# rapoukBoardv6.net
KiCad netlist of a schematic drawn in EasyEDA
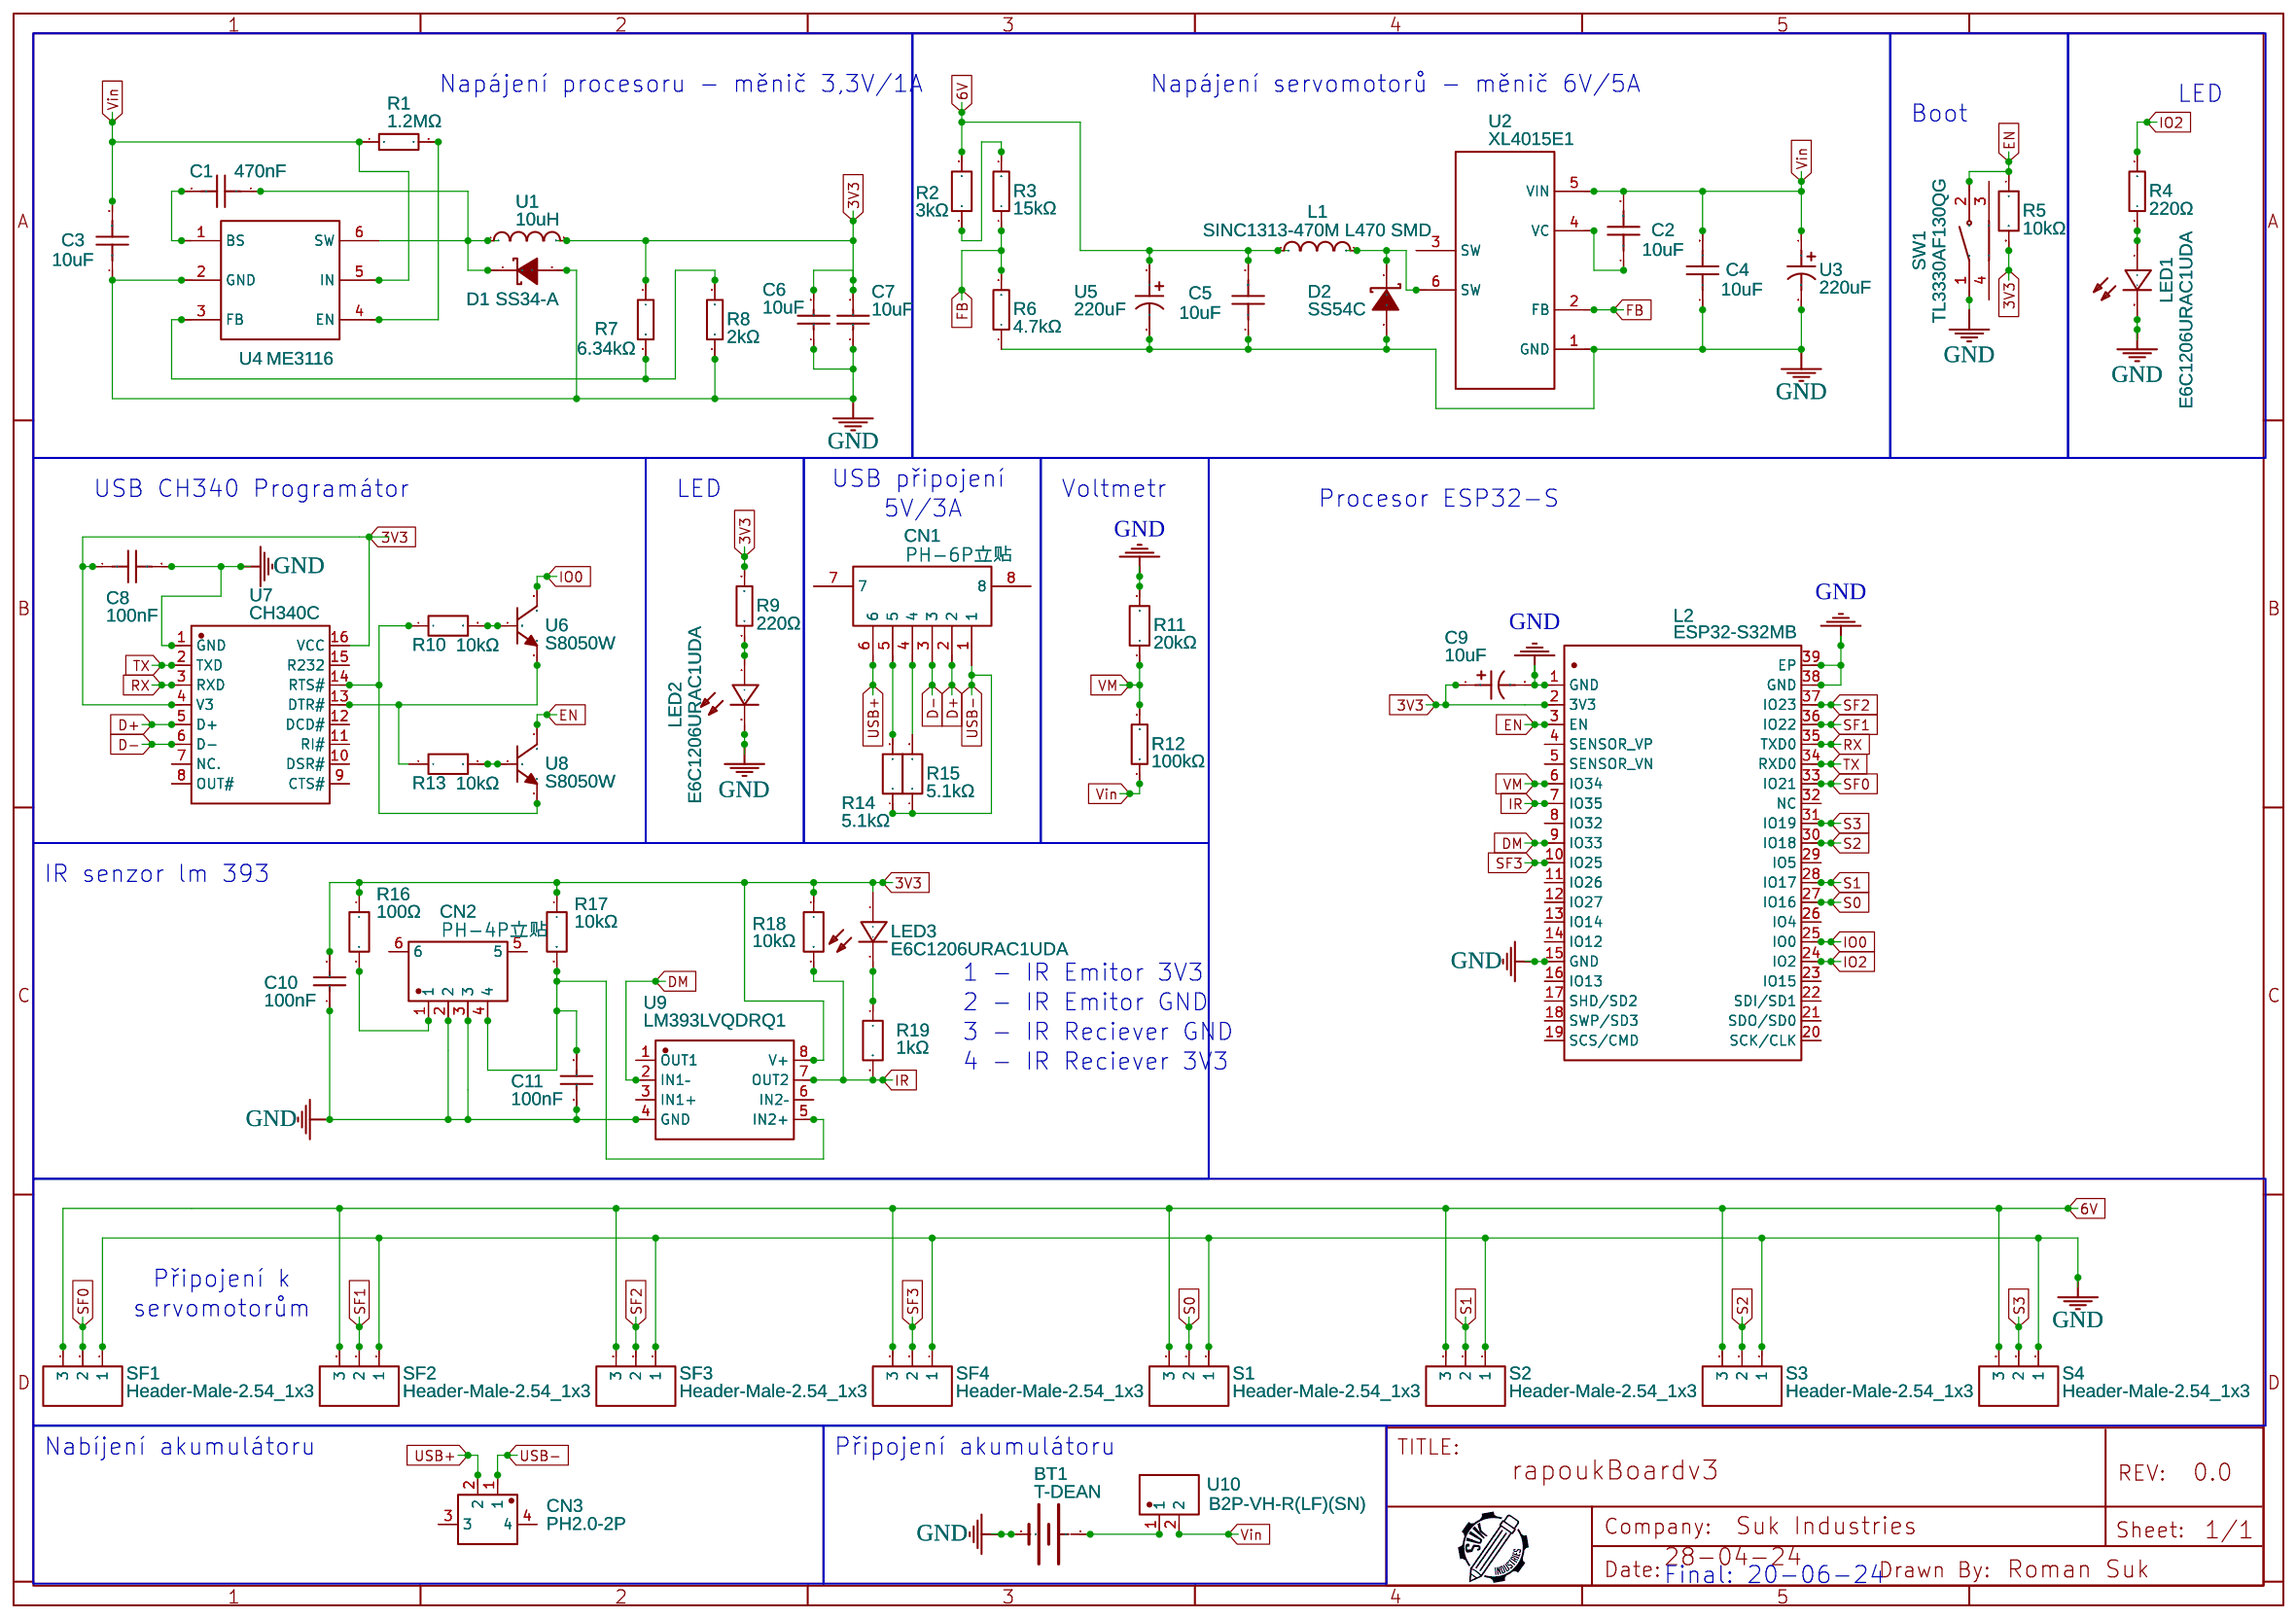
[diagram p0: schematic sheet]

(export (version "E")
  (design (tool "Eeschema 10.0.6"))
  (components
    (comp (ref "BT1") (value "T-DEAN") (libsource (lib "") (part "T-DEAN")))
    (comp (ref "C1")
      (value "470nF")
      (fields
        (field (name "Manufacturer Part") "TCC1206X7R474K500FT")
        (field (name "Manufacturer") "CCTC(三环)")
      )
      (libsource (lib "") (part "TCC1206X7R474K500FT"))
    )
    (comp (ref "C2")
      (value "10uF")
      (fields
        (field (name "Manufacturer Part") "TCC1206X7R106K250HT")
        (field (name "Manufacturer") "CCTC(三环)")
      )
      (libsource (lib "") (part "TCC1206X7R106K250HT"))
    )
    (comp (ref "C3")
      (value "10uF")
      (fields
        (field (name "Manufacturer Part") "TCC1206X7R106K250HT")
        (field (name "Manufacturer") "CCTC(三环)")
      )
      (libsource (lib "") (part "TCC1206X7R106K250HT"))
    )
    (comp (ref "C4")
      (value "10uF")
      (fields
        (field (name "Manufacturer Part") "TCC1206X7R106K250HT")
        (field (name "Manufacturer") "CCTC(三环)")
      )
      (libsource (lib "") (part "TCC1206X7R106K250HT"))
    )
    (comp (ref "C5")
      (value "10uF")
      (fields
        (field (name "Manufacturer Part") "TCC1206X7R106K250HT")
        (field (name "Manufacturer") "CCTC(三环)")
      )
      (libsource (lib "") (part "TCC1206X7R106K250HT"))
    )
    (comp (ref "C6")
      (value "10uF")
      (fields
        (field (name "Manufacturer Part") "TMK316B7106KL-TD")
        (field (name "Manufacturer") "TAIYO YUDEN(太诱)")
      )
      (libsource (lib "") (part "TMK316B7106KL-TD"))
    )
    (comp (ref "C7")
      (value "10uF")
      (fields
        (field (name "Manufacturer Part") "TMK316B7106KL-TD")
        (field (name "Manufacturer") "TAIYO YUDEN(太诱)")
      )
      (libsource (lib "") (part "TMK316B7106KL-TD"))
    )
    (comp (ref "C8")
      (value "100nF")
      (fields
        (field (name "Manufacturer Part") "1206Y1000104KXR")
        (field (name "Manufacturer") "Knowles(楼氏)")
      )
      (libsource (lib "") (part "1206Y1000104KXR"))
    )
    (comp (ref "C9")
      (value "10uF")
      (fields (field (name "Manufacturer Part") "RST10UF16V013") (field (name "Manufacturer") "KNSCHA(科尼盛)"))
      (libsource (lib "") (part "RST10UF16V013"))
    )
    (comp (ref "C10")
      (value "100nF")
      (fields (field (name "Manufacturer Part") "C1206X104K451T") (field (name "Manufacturer") "IHHEC(禾伸堂)"))
      (libsource (lib "") (part "C1206X104K451T"))
    )
    (comp (ref "C11")
      (value "100nF")
      (fields (field (name "Manufacturer Part") "C1206X104K451T") (field (name "Manufacturer") "IHHEC(禾伸堂)"))
      (libsource (lib "") (part "C1206X104K451T"))
    )
    (comp (ref "CN1")
      (value "PH-6P立贴")
      (fields (field (name "Manufacturer") "BOOMELE(博穆精密)"))
      (libsource (lib "") (part "PH-6P立贴"))
    )
    (comp (ref "CN2")
      (value "PH-4P立贴")
      (fields (field (name "Manufacturer") "BOOMELE(博穆精密)"))
      (libsource (lib "") (part "PH-4P立贴"))
    )
    (comp (ref "CN3")
      (value "PH2.0-2P")
      (fields (field (name "Manufacturer Part") "PH-2P立贴") (field (name "Manufacturer") "BOOMELE(博穆精密)"))
      (libsource (lib "") (part "PH2.0-2P"))
    )
    (comp (ref "D1")
      (value "SS34-A")
      (fields (field (name "Manufacturer") "FMS(美丽微)"))
      (libsource (lib "") (part "SS34-A"))
    )
    (comp (ref "D2")
      (value "SS54C")
      (fields (field (name "Manufacturer Part") "SS54") (field (name "Manufacturer") "LGE(鲁光)"))
      (libsource (lib "") (part "SS54C"))
    )
    (comp (ref "L1") (value "SINC1313-470M L470 SMD") (libsource (lib "") (part "SINC1313-470M L470 SMD")))
    (comp (ref "L2")
      (value "ESP32-S32MB")
      (fields
        (field (name "Manufacturer Part") "ESP32-S32Mb")
        (field (name "Manufacturer") "Ai-Thinker(安信可)")
      )
      (libsource (lib "") (part "ESP32-S32MB"))
    )
    (comp (ref "LED1")
      (value "E6C1206URAC1UDA")
      (fields (field (name "Manufacturer") "ekinglux(亿晶源)"))
      (libsource (lib "") (part "E6C1206URAC1UDA"))
    )
    (comp (ref "LED2")
      (value "E6C1206URAC1UDA")
      (fields (field (name "Manufacturer") "ekinglux(亿晶源)"))
      (libsource (lib "") (part "E6C1206URAC1UDA"))
    )
    (comp (ref "LED3")
      (value "E6C1206URAC1UDA")
      (fields (field (name "Manufacturer") "ekinglux(亿晶源)"))
      (libsource (lib "") (part "E6C1206URAC1UDA"))
    )
    (comp (ref "R1")
      (value "1.2MΩ")
      (fields (field (name "Manufacturer Part") "WR12W1204FTL") (field (name "Manufacturer") "Walsin(华新科)"))
      (libsource (lib "") (part "WR12W1204FTL"))
    )
    (comp (ref "R2")
      (value "3kΩ")
      (fields
        (field (name "Manufacturer Part") "CR1206J3K00P05Z")
        (field (name "Manufacturer") "EVER OHMS(天二科技)")
      )
      (libsource (lib "") (part "CR1206J3K00P05Z"))
    )
    (comp (ref "R3")
      (value "15kΩ")
      (fields (field (name "Manufacturer Part") "RT1206FRD0715KL") (field (name "Manufacturer") "YAGEO(国巨)"))
      (libsource (lib "") (part "RT1206FRD0715KL"))
    )
    (comp (ref "R4")
      (value "220Ω")
      (fields (field (name "Manufacturer Part") "AECR1206F220RK9") (field (name "Manufacturer") "RESI(开步睿思）"))
      (libsource (lib "") (part "AECR1206F220RK9"))
    )
    (comp (ref "R5")
      (value "10kΩ")
      (fields (field (name "Manufacturer Part") "SCR1206F10K") (field (name "Manufacturer") "VO(翔胜)"))
      (libsource (lib "") (part "SCR1206F10K"))
    )
    (comp (ref "R6")
      (value "4.7kΩ")
      (fields
        (field (name "Manufacturer Part") "CRCW12064K70FKEA")
        (field (name "Manufacturer") "VISHAY(威世)")
      )
      (libsource (lib "") (part "CRCW12064K70FKEA"))
    )
    (comp (ref "R7")
      (value "6.34kΩ")
      (fields (field (name "Manufacturer Part") "RS-06K6341FT") (field (name "Manufacturer") "FH(风华)"))
      (libsource (lib "") (part "RS-06K6341FT"))
    )
    (comp (ref "R8")
      (value "2kΩ")
      (fields (field (name "Manufacturer Part") "RTT06202JTP") (field (name "Manufacturer") "RALEC(旺诠)"))
      (libsource (lib "") (part "RTT06202JTP"))
    )
    (comp (ref "R9")
      (value "220Ω")
      (fields (field (name "Manufacturer Part") "AECR1206F220RK9") (field (name "Manufacturer") "RESI(开步睿思）"))
      (libsource (lib "") (part "AECR1206F220RK9"))
    )
    (comp (ref "R10")
      (value "10kΩ")
      (fields (field (name "Manufacturer Part") "SCR1206F10K") (field (name "Manufacturer") "VO(翔胜)"))
      (libsource (lib "") (part "SCR1206F10K_1"))
    )
    (comp (ref "R11")
      (value "20kΩ")
      (fields
        (field (name "Manufacturer Part") "CR1206F20KP05")
        (field (name "Manufacturer") "EVER OHMS(天二科技)")
      )
      (libsource (lib "") (part "CR1206F20KP05"))
    )
    (comp (ref "R12")
      (value "100kΩ")
      (fields
        (field (name "Manufacturer Part") "QR1206F100KP05Z")
        (field (name "Manufacturer") "EVER OHMS(天二科技)")
      )
      (libsource (lib "") (part "QR1206F100KP05"))
    )
    (comp (ref "R13")
      (value "10kΩ")
      (fields (field (name "Manufacturer Part") "SCR1206F10K") (field (name "Manufacturer") "VO(翔胜)"))
      (libsource (lib "") (part "SCR1206F10K_1"))
    )
    (comp (ref "R14")
      (value "5.1kΩ")
      (fields (field (name "Manufacturer Part") "RT1206BRD075KL") (field (name "Manufacturer") "YAGEO(国巨)"))
      (libsource (lib "") (part "RT1206BRD075KL"))
    )
    (comp (ref "R15")
      (value "5.1kΩ")
      (fields (field (name "Manufacturer Part") "RT1206BRD075KL") (field (name "Manufacturer") "YAGEO(国巨)"))
      (libsource (lib "") (part "RT1206BRD075KL"))
    )
    (comp (ref "R16")
      (value "100Ω")
      (fields (field (name "Manufacturer Part") "SCR1206F100R") (field (name "Manufacturer") "VO(翔胜)"))
      (libsource (lib "") (part "SCR1206F100R"))
    )
    (comp (ref "R17")
      (value "10kΩ")
      (fields (field (name "Manufacturer Part") "SCR1206F10K") (field (name "Manufacturer") "VO(翔胜)"))
      (libsource (lib "") (part "SCR1206F10K"))
    )
    (comp (ref "R18")
      (value "10kΩ")
      (fields (field (name "Manufacturer Part") "SCR1206F10K") (field (name "Manufacturer") "VO(翔胜)"))
      (libsource (lib "") (part "SCR1206F10K"))
    )
    (comp (ref "R19")
      (value "1kΩ")
      (fields (field (name "Manufacturer Part") "SCR1206J1K") (field (name "Manufacturer") "VO(翔胜)"))
      (libsource (lib "") (part "SCR1206J1K"))
    )
    (comp (ref "S1")
      (value "Header-Male-2.54_1x3")
      (fields (field (name "Manufacturer Part") "2.54-1*3P针") (field (name "Manufacturer") "BOOMELE(博穆精密)"))
      (libsource (lib "") (part "Header-Male-2.54_1x3_1"))
    )
    (comp (ref "S2")
      (value "Header-Male-2.54_1x3")
      (fields (field (name "Manufacturer Part") "2.54-1*3P针") (field (name "Manufacturer") "BOOMELE(博穆精密)"))
      (libsource (lib "") (part "Header-Male-2.54_1x3_1"))
    )
    (comp (ref "S3")
      (value "Header-Male-2.54_1x3")
      (fields (field (name "Manufacturer Part") "2.54-1*3P针") (field (name "Manufacturer") "BOOMELE(博穆精密)"))
      (libsource (lib "") (part "Header-Male-2.54_1x3_1"))
    )
    (comp (ref "S4")
      (value "Header-Male-2.54_1x3")
      (fields (field (name "Manufacturer Part") "2.54-1*3P针") (field (name "Manufacturer") "BOOMELE(博穆精密)"))
      (libsource (lib "") (part "Header-Male-2.54_1x3_1"))
    )
    (comp (ref "SF1")
      (value "Header-Male-2.54_1x3")
      (fields (field (name "Manufacturer Part") "2.54-1*3P针") (field (name "Manufacturer") "BOOMELE(博穆精密)"))
      (libsource (lib "") (part "Header-Male-2.54_1x3"))
    )
    (comp (ref "SF2")
      (value "Header-Male-2.54_1x3")
      (fields (field (name "Manufacturer Part") "2.54-1*3P针") (field (name "Manufacturer") "BOOMELE(博穆精密)"))
      (libsource (lib "") (part "Header-Male-2.54_1x3"))
    )
    (comp (ref "SF3")
      (value "Header-Male-2.54_1x3")
      (fields (field (name "Manufacturer Part") "2.54-1*3P针") (field (name "Manufacturer") "BOOMELE(博穆精密)"))
      (libsource (lib "") (part "Header-Male-2.54_1x3"))
    )
    (comp (ref "SF4")
      (value "Header-Male-2.54_1x3")
      (fields (field (name "Manufacturer Part") "2.54-1*3P针") (field (name "Manufacturer") "BOOMELE(博穆精密)"))
      (libsource (lib "") (part "Header-Male-2.54_1x3"))
    )
    (comp (ref "SW1")
      (value "TL3330AF130QG")
      (fields (field (name "Manufacturer") "E-Switch"))
      (libsource (lib "") (part "TL3330AF130QG"))
    )
    (comp (ref "U1")
      (value "10uH")
      (fields
        (field (name "Manufacturer Part") "CD54YP0504-100M")
        (field (name "Manufacturer") "YJYCOIN(益嘉源)")
      )
      (libsource (lib "") (part "CD54YP0504-100M"))
    )
    (comp (ref "U2")
      (value "XL4015E1")
      (fields (field (name "Manufacturer") "XLSEMI(芯龙)"))
      (libsource (lib "") (part "XL4015E1"))
    )
    (comp (ref "U3")
      (value "220uF")
      (fields
        (field (name "Manufacturer Part") "CK220UF16V167RV0142")
        (field (name "Manufacturer") "KNSCHA(科尼盛)")
      )
      (libsource (lib "") (part "CK220UF16V167RV0142"))
    )
    (comp (ref "U4")
      (value "ME3116")
      (fields (field (name "Manufacturer Part") "ME3116AM6G") (field (name "Manufacturer") "MICRONE(南京微盟)"))
      (libsource (lib "") (part "ME3116"))
    )
    (comp (ref "U5")
      (value "220uF")
      (fields
        (field (name "Manufacturer Part") "CK220UF16V167RV0142")
        (field (name "Manufacturer") "KNSCHA(科尼盛)")
      )
      (libsource (lib "") (part "CK220UF16V167RV0142"))
    )
    (comp (ref "U6")
      (value "S8050W")
      (fields (field (name "Manufacturer") "Slkor(萨科微)"))
      (libsource (lib "") (part "S8050W"))
    )
    (comp (ref "U7")
      (value "CH340C")
      (fields (field (name "Manufacturer") "WCH(南京沁恒)"))
      (libsource (lib "") (part "CH340C"))
    )
    (comp (ref "U8")
      (value "S8050W")
      (fields (field (name "Manufacturer") "Slkor(萨科微)"))
      (libsource (lib "") (part "S8050W"))
    )
    (comp (ref "U9")
      (value "LM393LVQDRQ1")
      (fields (field (name "Manufacturer") "TI(德州仪器)"))
      (libsource (lib "") (part "LM393LVQDRQ1"))
    )
    (comp (ref "U10")
      (value "B2P-VH-R(LF)(SN)")
      (fields (field (name "Manufacturer") "JST"))
      (libsource (lib "") (part "B2P-VH-R(LF)(SN)"))
    )
  )
  (nets
    (net (code "1") (name "3V3") (class "Default")
      (node (ref "C10") (pin "2") (pinfunction "2_2") (pintype "input"))
      (node (ref "C6") (pin "2") (pinfunction "2_2") (pintype "input"))
      (node (ref "C7") (pin "2") (pinfunction "2_2") (pintype "input"))
      (node (ref "C8") (pin "1") (pinfunction "1_1") (pintype "unspecified"))
      (node (ref "C9") (pin "1") (pinfunction "1_1") (pintype "input"))
      (node (ref "L2") (pin "2") (pinfunction "3V3_2") (pintype "unspecified"))
      (node (ref "LED3") (pin "1") (pinfunction "+_1") (pintype "unspecified"))
      (node (ref "R16") (pin "1") (pinfunction "1_1") (pintype "unspecified"))
      (node (ref "R17") (pin "1") (pinfunction "1_1") (pintype "unspecified"))
      (node (ref "R18") (pin "1") (pinfunction "1_1") (pintype "unspecified"))
      (node (ref "R5") (pin "2") (pinfunction "2_2") (pintype "unspecified"))
      (node (ref "R7") (pin "1") (pinfunction "1_1") (pintype "unspecified"))
      (node (ref "R9") (pin "2") (pinfunction "2_2") (pintype "unspecified"))
      (node (ref "U1") (pin "2") (pinfunction "2_2") (pintype "unspecified"))
      (node (ref "U7") (pin "16") (pinfunction "VCC_16") (pintype "unspecified"))
      (node (ref "U7") (pin "4") (pinfunction "V3_4") (pintype "unspecified"))
      (node (ref "U9") (pin "8") (pinfunction "V+_8") (pintype "unspecified"))
    )
    (net (code "2") (name "6V") (class "Default")
      (node (ref "C5") (pin "2") (pinfunction "2_2") (pintype "unspecified"))
      (node (ref "L1") (pin "1") (pinfunction "1_1") (pintype "unspecified"))
      (node (ref "R2") (pin "2") (pinfunction "2_2") (pintype "unspecified"))
      (node (ref "S1") (pin "3") (pinfunction "3_3") (pintype "input"))
      (node (ref "S2") (pin "3") (pinfunction "3_3") (pintype "input"))
      (node (ref "S3") (pin "3") (pinfunction "3_3") (pintype "input"))
      (node (ref "S4") (pin "3") (pinfunction "3_3") (pintype "input"))
      (node (ref "SF1") (pin "3") (pinfunction "3_3") (pintype "input"))
      (node (ref "SF2") (pin "3") (pinfunction "3_3") (pintype "input"))
      (node (ref "SF3") (pin "3") (pinfunction "3_3") (pintype "input"))
      (node (ref "SF4") (pin "3") (pinfunction "3_3") (pintype "input"))
      (node (ref "U5") (pin "1") (pinfunction "1_1") (pintype "input"))
    )
    (net (code "3") (name "D+") (class "Default")
      (node (ref "CN1") (pin "2") (pinfunction "2_2") (pintype "unspecified"))
      (node (ref "U7") (pin "5") (pinfunction "D+_5") (pintype "unspecified"))
    )
    (net (code "4") (name "D-") (class "Default")
      (node (ref "CN1") (pin "3") (pinfunction "3_3") (pintype "unspecified"))
      (node (ref "U7") (pin "6") (pinfunction "D-_6") (pintype "unspecified"))
    )
    (net (code "5") (name "DM") (class "Default")
      (node (ref "L2") (pin "9") (pinfunction "IO33_9") (pintype "unspecified"))
      (node (ref "U9") (pin "2") (pinfunction "IN1–_2") (pintype "unspecified"))
    )
    (net (code "6") (name "EN") (class "Default")
      (node (ref "L2") (pin "3") (pinfunction "EN_3") (pintype "unspecified"))
      (node (ref "R5") (pin "1") (pinfunction "1_1") (pintype "unspecified"))
      (node (ref "SW1") (pin "2") (pinfunction "2_2") (pintype "unspecified"))
      (node (ref "U8") (pin "3") (pinfunction "C_3") (pintype "unspecified"))
    )
    (net (code "7") (name "FB") (class "Default")
      (node (ref "R3") (pin "1") (pinfunction "1_1") (pintype "unspecified"))
      (node (ref "R6") (pin "2") (pinfunction "2_2") (pintype "unspecified"))
      (node (ref "U2") (pin "2") (pinfunction "FB_2") (pintype "unspecified"))
    )
    (net (code "8") (name "GND") (class "Default")
      (node (ref "BT1") (pin "2") (pinfunction "2_2") (pintype "bidirectional"))
      (node (ref "C10") (pin "1") (pinfunction "1_1") (pintype "input"))
      (node (ref "C11") (pin "1") (pinfunction "1_1") (pintype "input"))
      (node (ref "C3") (pin "1") (pinfunction "1_1") (pintype "unspecified"))
      (node (ref "C4") (pin "1") (pinfunction "1_1") (pintype "unspecified"))
      (node (ref "C5") (pin "1") (pinfunction "1_1") (pintype "unspecified"))
      (node (ref "C6") (pin "1") (pinfunction "1_1") (pintype "input"))
      (node (ref "C7") (pin "1") (pinfunction "1_1") (pintype "input"))
      (node (ref "C8") (pin "2") (pinfunction "2_2") (pintype "unspecified"))
      (node (ref "C9") (pin "2") (pinfunction "2_2") (pintype "input"))
      (node (ref "CN2") (pin "2") (pinfunction "2_2") (pintype "unspecified"))
      (node (ref "CN2") (pin "3") (pinfunction "3_3") (pintype "unspecified"))
      (node (ref "D1") (pin "2") (pinfunction "A_2") (pintype "unspecified"))
      (node (ref "D2") (pin "2") (pinfunction "A_2") (pintype "unspecified"))
      (node (ref "L2") (pin "1") (pinfunction "GND_1") (pintype "unspecified"))
      (node (ref "L2") (pin "15") (pinfunction "GND_15") (pintype "unspecified"))
      (node (ref "L2") (pin "38") (pinfunction "GND_38") (pintype "unspecified"))
      (node (ref "L2") (pin "39") (pinfunction "EP_39") (pintype "unspecified"))
      (node (ref "LED1") (pin "2") (pinfunction "-_2") (pintype "unspecified"))
      (node (ref "LED2") (pin "2") (pinfunction "-_2") (pintype "unspecified"))
      (node (ref "R11") (pin "2") (pinfunction "2_2") (pintype "unspecified"))
      (node (ref "R6") (pin "1") (pinfunction "1_1") (pintype "unspecified"))
      (node (ref "R8") (pin "1") (pinfunction "1_1") (pintype "input"))
      (node (ref "S1") (pin "1") (pinfunction "1_1") (pintype "input"))
      (node (ref "S2") (pin "1") (pinfunction "1_1") (pintype "input"))
      (node (ref "S3") (pin "1") (pinfunction "1_1") (pintype "input"))
      (node (ref "S4") (pin "1") (pinfunction "1_1") (pintype "input"))
      (node (ref "SF1") (pin "1") (pinfunction "1_1") (pintype "input"))
      (node (ref "SF2") (pin "1") (pinfunction "1_1") (pintype "input"))
      (node (ref "SF3") (pin "1") (pinfunction "1_1") (pintype "input"))
      (node (ref "SF4") (pin "1") (pinfunction "1_1") (pintype "input"))
      (node (ref "SW1") (pin "1") (pinfunction "1_1") (pintype "unspecified"))
      (node (ref "U2") (pin "1") (pinfunction "GND_1") (pintype "unspecified"))
      (node (ref "U3") (pin "2") (pinfunction "2_2") (pintype "input"))
      (node (ref "U4") (pin "2") (pinfunction "GND_2") (pintype "unspecified"))
      (node (ref "U5") (pin "2") (pinfunction "2_2") (pintype "input"))
      (node (ref "U7") (pin "1") (pinfunction "GND_1") (pintype "unspecified"))
      (node (ref "U9") (pin "4") (pinfunction "GND_4") (pintype "unspecified"))
    )
    (net (code "9") (name "IO0") (class "Default")
      (node (ref "L2") (pin "25") (pinfunction "IO0_25") (pintype "unspecified"))
      (node (ref "U6") (pin "3") (pinfunction "C_3") (pintype "unspecified"))
    )
    (net (code "10") (name "IO2") (class "Default")
      (node (ref "L2") (pin "24") (pinfunction "IO2_24") (pintype "unspecified"))
      (node (ref "R4") (pin "2") (pinfunction "2_2") (pintype "unspecified"))
    )
    (net (code "11") (name "IR") (class "Default")
      (node (ref "L2") (pin "7") (pinfunction "IO35_7") (pintype "unspecified"))
      (node (ref "R18") (pin "2") (pinfunction "2_2") (pintype "unspecified"))
      (node (ref "R19") (pin "2") (pinfunction "2_2") (pintype "unspecified"))
      (node (ref "U9") (pin "7") (pinfunction "OUT2_7") (pintype "unspecified"))
    )
    (net (code "12") (name "Net-(BT1-Pad1)") (class "Default")
      (node (ref "BT1") (pin "1") (pinfunction "1_1") (pintype "bidirectional"))
      (node (ref "U10") (pin "1") (pinfunction "1_1") (pintype "unspecified"))
    )
    (net (code "13") (name "Net-(CN1-Pad4)") (class "Default")
      (node (ref "CN1") (pin "4") (pinfunction "4_4") (pintype "unspecified"))
      (node (ref "R15") (pin "2") (pinfunction "2_2") (pintype "unspecified"))
    )
    (net (code "14") (name "Net-(CN1-Pad5)") (class "Default")
      (node (ref "CN1") (pin "5") (pinfunction "5_5") (pintype "unspecified"))
      (node (ref "R14") (pin "2") (pinfunction "2_2") (pintype "unspecified"))
    )
    (net (code "15") (name "Net-(CN2-Pad1)") (class "Default")
      (node (ref "CN2") (pin "1") (pinfunction "1_1") (pintype "unspecified"))
      (node (ref "R16") (pin "2") (pinfunction "2_2") (pintype "unspecified"))
    )
    (net (code "16") (name "Net-(D1-C)") (class "Default")
      (node (ref "C1") (pin "1") (pinfunction "1_1") (pintype "unspecified"))
      (node (ref "D1") (pin "1") (pinfunction "C_1") (pintype "unspecified"))
      (node (ref "U1") (pin "1") (pinfunction "1_1") (pintype "unspecified"))
      (node (ref "U4") (pin "6") (pinfunction "SW_6") (pintype "unspecified"))
    )
    (net (code "17") (name "Net-(D2-K)") (class "Default")
      (node (ref "D2") (pin "1") (pinfunction "K_1") (pintype "unspecified"))
      (node (ref "L1") (pin "2") (pinfunction "2_2") (pintype "unspecified"))
      (node (ref "U2") (pin "6") (pinfunction "SW_6") (pintype "unspecified"))
    )
    (net (code "18") (name "Net-(LED1-+)") (class "Default")
      (node (ref "LED1") (pin "1") (pinfunction "+_1") (pintype "unspecified"))
      (node (ref "R4") (pin "1") (pinfunction "1_1") (pintype "unspecified"))
    )
    (net (code "19") (name "Net-(LED2-+)") (class "Default")
      (node (ref "LED2") (pin "1") (pinfunction "+_1") (pintype "unspecified"))
      (node (ref "R9") (pin "1") (pinfunction "1_1") (pintype "unspecified"))
    )
    (net (code "20") (name "Net-(LED3--)") (class "Default")
      (node (ref "LED3") (pin "2") (pinfunction "-_2") (pintype "unspecified"))
      (node (ref "R19") (pin "1") (pinfunction "1_1") (pintype "unspecified"))
    )
    (net (code "21") (name "Net-(R2-Pad1)") (class "Default")
      (node (ref "R2") (pin "1") (pinfunction "1_1") (pintype "unspecified"))
      (node (ref "R3") (pin "2") (pinfunction "2_2") (pintype "unspecified"))
    )
    (net (code "22") (name "Net-(U2-VC)") (class "Default")
      (node (ref "C2") (pin "1") (pinfunction "1_1") (pintype "unspecified"))
      (node (ref "U2") (pin "4") (pinfunction "VC_4") (pintype "unspecified"))
    )
    (net (code "23") (name "Net-(U4-BS)") (class "Default")
      (node (ref "C1") (pin "2") (pinfunction "2_2") (pintype "unspecified"))
      (node (ref "U4") (pin "1") (pinfunction "BS_1") (pintype "unspecified"))
    )
    (net (code "24") (name "Net-(U4-EN)") (class "Default")
      (node (ref "R1") (pin "2") (pinfunction "2_2") (pintype "unspecified"))
      (node (ref "U4") (pin "4") (pinfunction "EN_4") (pintype "unspecified"))
    )
    (net (code "25") (name "Net-(U4-FB)") (class "Default")
      (node (ref "R7") (pin "2") (pinfunction "2_2") (pintype "unspecified"))
      (node (ref "R8") (pin "2") (pinfunction "2_2") (pintype "input"))
      (node (ref "U4") (pin "3") (pinfunction "FB_3") (pintype "unspecified"))
    )
    (net (code "26") (name "Net-(U6-B)") (class "Default")
      (node (ref "R10") (pin "2") (pinfunction "2_2") (pintype "unspecified"))
      (node (ref "U6") (pin "1") (pinfunction "B_1") (pintype "unspecified"))
    )
    (net (code "27") (name "Net-(U6-E)") (class "Default")
      (node (ref "R13") (pin "1") (pinfunction "1_1") (pintype "unspecified"))
      (node (ref "U6") (pin "2") (pinfunction "E_2") (pintype "unspecified"))
      (node (ref "U7") (pin "13") (pinfunction "DTR#_13") (pintype "unspecified"))
    )
    (net (code "28") (name "Net-(U7-RTS#)") (class "Default")
      (node (ref "R10") (pin "1") (pinfunction "1_1") (pintype "unspecified"))
      (node (ref "U7") (pin "14") (pinfunction "RTS#_14") (pintype "unspecified"))
      (node (ref "U8") (pin "2") (pinfunction "E_2") (pintype "unspecified"))
    )
    (net (code "29") (name "Net-(U8-B)") (class "Default")
      (node (ref "R13") (pin "2") (pinfunction "2_2") (pintype "unspecified"))
      (node (ref "U8") (pin "1") (pinfunction "B_1") (pintype "unspecified"))
    )
    (net (code "30") (name "Net-(U9-IN2+)") (class "Default")
      (node (ref "C11") (pin "2") (pinfunction "2_2") (pintype "input"))
      (node (ref "CN2") (pin "4") (pinfunction "4_4") (pintype "unspecified"))
      (node (ref "R17") (pin "2") (pinfunction "2_2") (pintype "unspecified"))
      (node (ref "U9") (pin "5") (pinfunction "IN2+_5") (pintype "unspecified"))
    )
    (net (code "31") (name "RX") (class "Default")
      (node (ref "L2") (pin "35") (pinfunction "TXD0_35") (pintype "unspecified"))
      (node (ref "U7") (pin "3") (pinfunction "RXD_3") (pintype "unspecified"))
    )
    (net (code "32") (name "S0") (class "Default")
      (node (ref "L2") (pin "27") (pinfunction "IO16_27") (pintype "unspecified"))
      (node (ref "S1") (pin "2") (pinfunction "2_2") (pintype "input"))
    )
    (net (code "33") (name "S1") (class "Default")
      (node (ref "L2") (pin "28") (pinfunction "IO17_28") (pintype "unspecified"))
      (node (ref "S2") (pin "2") (pinfunction "2_2") (pintype "input"))
    )
    (net (code "34") (name "S2") (class "Default")
      (node (ref "L2") (pin "30") (pinfunction "IO18_30") (pintype "unspecified"))
      (node (ref "S3") (pin "2") (pinfunction "2_2") (pintype "input"))
    )
    (net (code "35") (name "S3") (class "Default")
      (node (ref "L2") (pin "31") (pinfunction "IO19_31") (pintype "unspecified"))
      (node (ref "S4") (pin "2") (pinfunction "2_2") (pintype "input"))
    )
    (net (code "36") (name "SF0") (class "Default")
      (node (ref "L2") (pin "33") (pinfunction "IO21_33") (pintype "unspecified"))
      (node (ref "SF1") (pin "2") (pinfunction "2_2") (pintype "input"))
    )
    (net (code "37") (name "SF1") (class "Default")
      (node (ref "L2") (pin "36") (pinfunction "IO22_36") (pintype "unspecified"))
      (node (ref "SF2") (pin "2") (pinfunction "2_2") (pintype "input"))
    )
    (net (code "38") (name "SF2") (class "Default")
      (node (ref "L2") (pin "37") (pinfunction "IO23_37") (pintype "unspecified"))
      (node (ref "SF3") (pin "2") (pinfunction "2_2") (pintype "input"))
    )
    (net (code "39") (name "SF3") (class "Default")
      (node (ref "L2") (pin "10") (pinfunction "IO25_10") (pintype "unspecified"))
      (node (ref "SF4") (pin "2") (pinfunction "2_2") (pintype "input"))
    )
    (net (code "40") (name "TX") (class "Default")
      (node (ref "L2") (pin "34") (pinfunction "RXD0_34") (pintype "unspecified"))
      (node (ref "U7") (pin "2") (pinfunction "TXD_2") (pintype "unspecified"))
    )
    (net (code "41") (name "USB+") (class "Default")
      (node (ref "CN1") (pin "6") (pinfunction "6_6") (pintype "unspecified"))
      (node (ref "CN3") (pin "2") (pinfunction "2_2") (pintype "unspecified"))
    )
    (net (code "42") (name "USB-") (class "Default")
      (node (ref "CN1") (pin "1") (pinfunction "1_1") (pintype "unspecified"))
      (node (ref "CN3") (pin "1") (pinfunction "1_1") (pintype "unspecified"))
      (node (ref "R14") (pin "1") (pinfunction "1_1") (pintype "unspecified"))
      (node (ref "R15") (pin "1") (pinfunction "1_1") (pintype "unspecified"))
    )
    (net (code "43") (name "VM") (class "Default")
      (node (ref "L2") (pin "6") (pinfunction "IO34_6") (pintype "unspecified"))
      (node (ref "R11") (pin "1") (pinfunction "1_1") (pintype "unspecified"))
      (node (ref "R12") (pin "2") (pinfunction "2_2") (pintype "unspecified"))
    )
    (net (code "44") (name "Vin") (class "Default")
      (node (ref "C2") (pin "2") (pinfunction "2_2") (pintype "unspecified"))
      (node (ref "C3") (pin "2") (pinfunction "2_2") (pintype "unspecified"))
      (node (ref "C4") (pin "2") (pinfunction "2_2") (pintype "unspecified"))
      (node (ref "R1") (pin "1") (pinfunction "1_1") (pintype "unspecified"))
      (node (ref "R12") (pin "1") (pinfunction "1_1") (pintype "unspecified"))
      (node (ref "U10") (pin "2") (pinfunction "2_2") (pintype "unspecified"))
      (node (ref "U2") (pin "5") (pinfunction "VIN_5") (pintype "unspecified"))
      (node (ref "U3") (pin "1") (pinfunction "1_1") (pintype "input"))
      (node (ref "U4") (pin "5") (pinfunction "IN_5") (pintype "unspecified"))
    )
    (net (code "45") (name "unconnected-(CN1-Pad7)") (class "Default")
      (node (ref "CN1") (pin "7") (pinfunction "7_7") (pintype "unspecified"))
    )
    (net (code "46") (name "unconnected-(CN1-Pad8)") (class "Default")
      (node (ref "CN1") (pin "8") (pinfunction "8_8") (pintype "unspecified"))
    )
    (net (code "47") (name "unconnected-(CN2-Pad5)") (class "Default")
      (node (ref "CN2") (pin "5") (pinfunction "5_5") (pintype "unspecified"))
    )
    (net (code "48") (name "unconnected-(CN2-Pad6)") (class "Default")
      (node (ref "CN2") (pin "6") (pinfunction "6_6") (pintype "unspecified"))
    )
    (net (code "49") (name "unconnected-(CN3-Pad3)") (class "Default")
      (node (ref "CN3") (pin "3") (pinfunction "3_3") (pintype "unspecified"))
    )
    (net (code "50") (name "unconnected-(CN3-Pad4)") (class "Default")
      (node (ref "CN3") (pin "4") (pinfunction "4_4") (pintype "unspecified"))
    )
    (net (code "51") (name "unconnected-(L2-IO4-Pad26)") (class "Default")
      (node (ref "L2") (pin "26") (pinfunction "IO4_26") (pintype "unspecified"))
    )
    (net (code "52") (name "unconnected-(L2-IO5-Pad29)") (class "Default")
      (node (ref "L2") (pin "29") (pinfunction "IO5_29") (pintype "unspecified"))
    )
    (net (code "53") (name "unconnected-(L2-IO12-Pad14)") (class "Default")
      (node (ref "L2") (pin "14") (pinfunction "IO12_14") (pintype "unspecified"))
    )
    (net (code "54") (name "unconnected-(L2-IO13-Pad16)") (class "Default")
      (node (ref "L2") (pin "16") (pinfunction "IO13_16") (pintype "unspecified"))
    )
    (net (code "55") (name "unconnected-(L2-IO14-Pad13)") (class "Default")
      (node (ref "L2") (pin "13") (pinfunction "IO14_13") (pintype "unspecified"))
    )
    (net (code "56") (name "unconnected-(L2-IO15-Pad23)") (class "Default")
      (node (ref "L2") (pin "23") (pinfunction "IO15_23") (pintype "unspecified"))
    )
    (net (code "57") (name "unconnected-(L2-IO26-Pad11)") (class "Default")
      (node (ref "L2") (pin "11") (pinfunction "IO26_11") (pintype "unspecified"))
    )
    (net (code "58") (name "unconnected-(L2-IO27-Pad12)") (class "Default")
      (node (ref "L2") (pin "12") (pinfunction "IO27_12") (pintype "unspecified"))
    )
    (net (code "59") (name "unconnected-(L2-IO32-Pad8)") (class "Default")
      (node (ref "L2") (pin "8") (pinfunction "IO32_8") (pintype "unspecified"))
    )
    (net (code "60") (name "unconnected-(L2-NC-Pad32)") (class "Default")
      (node (ref "L2") (pin "32") (pinfunction "NC_32") (pintype "unspecified"))
    )
    (net (code "61") (name "unconnected-(L2-SCK{slash}CLK-Pad20)") (class "Default")
      (node (ref "L2") (pin "20") (pinfunction "SCK/CLK_20") (pintype "unspecified"))
    )
    (net (code "62") (name "unconnected-(L2-SCS{slash}CMD-Pad19)") (class "Default")
      (node (ref "L2") (pin "19") (pinfunction "SCS/CMD_19") (pintype "unspecified"))
    )
    (net (code "63") (name "unconnected-(L2-SDI{slash}SD1-Pad22)") (class "Default")
      (node (ref "L2") (pin "22") (pinfunction "SDI/SD1_22") (pintype "unspecified"))
    )
    (net (code "64") (name "unconnected-(L2-SDO{slash}SD0-Pad21)") (class "Default")
      (node (ref "L2") (pin "21") (pinfunction "SDO/SD0_21") (pintype "unspecified"))
    )
    (net (code "65") (name "unconnected-(L2-SENSOR_VN-Pad5)") (class "Default")
      (node (ref "L2") (pin "5") (pinfunction "SENSOR_VN_5") (pintype "unspecified"))
    )
    (net (code "66") (name "unconnected-(L2-SENSOR_VP-Pad4)") (class "Default")
      (node (ref "L2") (pin "4") (pinfunction "SENSOR_VP_4") (pintype "unspecified"))
    )
    (net (code "67") (name "unconnected-(L2-SHD{slash}SD2-Pad17)") (class "Default")
      (node (ref "L2") (pin "17") (pinfunction "SHD/SD2_17") (pintype "unspecified"))
    )
    (net (code "68") (name "unconnected-(L2-SWP{slash}SD3-Pad18)") (class "Default")
      (node (ref "L2") (pin "18") (pinfunction "SWP/SD3_18") (pintype "unspecified"))
    )
    (net (code "69") (name "unconnected-(SW1-Pad3)") (class "Default")
      (node (ref "SW1") (pin "3") (pinfunction "3_3") (pintype "unspecified"))
    )
    (net (code "70") (name "unconnected-(SW1-Pad4)") (class "Default")
      (node (ref "SW1") (pin "4") (pinfunction "4_4") (pintype "unspecified"))
    )
    (net (code "71") (name "unconnected-(U2-SW-Pad3)") (class "Default")
      (node (ref "U2") (pin "3") (pinfunction "SW_3") (pintype "unspecified"))
    )
    (net (code "72") (name "unconnected-(U7-CTS#-Pad9)") (class "Default")
      (node (ref "U7") (pin "9") (pinfunction "CTS#_9") (pintype "unspecified"))
    )
    (net (code "73") (name "unconnected-(U7-DCD#-Pad12)") (class "Default")
      (node (ref "U7") (pin "12") (pinfunction "DCD#_12") (pintype "unspecified"))
    )
    (net (code "74") (name "unconnected-(U7-DSR#-Pad10)") (class "Default")
      (node (ref "U7") (pin "10") (pinfunction "DSR#_10") (pintype "unspecified"))
    )
    (net (code "75") (name "unconnected-(U7-NC.-Pad7)") (class "Default")
      (node (ref "U7") (pin "7") (pinfunction "NC._7") (pintype "unspecified"))
    )
    (net (code "76") (name "unconnected-(U7-OUT#-Pad8)") (class "Default")
      (node (ref "U7") (pin "8") (pinfunction "OUT#_8") (pintype "unspecified"))
    )
    (net (code "77") (name "unconnected-(U7-R232-Pad15)") (class "Default")
      (node (ref "U7") (pin "15") (pinfunction "R232_15") (pintype "unspecified"))
    )
    (net (code "78") (name "unconnected-(U7-RI#-Pad11)") (class "Default")
      (node (ref "U7") (pin "11") (pinfunction "RI#_11") (pintype "unspecified"))
    )
    (net (code "79") (name "unconnected-(U9-IN1+-Pad3)") (class "Default")
      (node (ref "U9") (pin "3") (pinfunction "IN1+_3") (pintype "unspecified"))
    )
    (net (code "80") (name "unconnected-(U9-IN2–-Pad6)") (class "Default")
      (node (ref "U9") (pin "6") (pinfunction "IN2–_6") (pintype "unspecified"))
    )
    (net (code "81") (name "unconnected-(U9-OUT1-Pad1)") (class "Default")
      (node (ref "U9") (pin "1") (pinfunction "OUT1_1") (pintype "unspecified"))
    )
  )
)
